# OtherSensors.net
KiCad netlist of a schematic drawn in Altium Designer
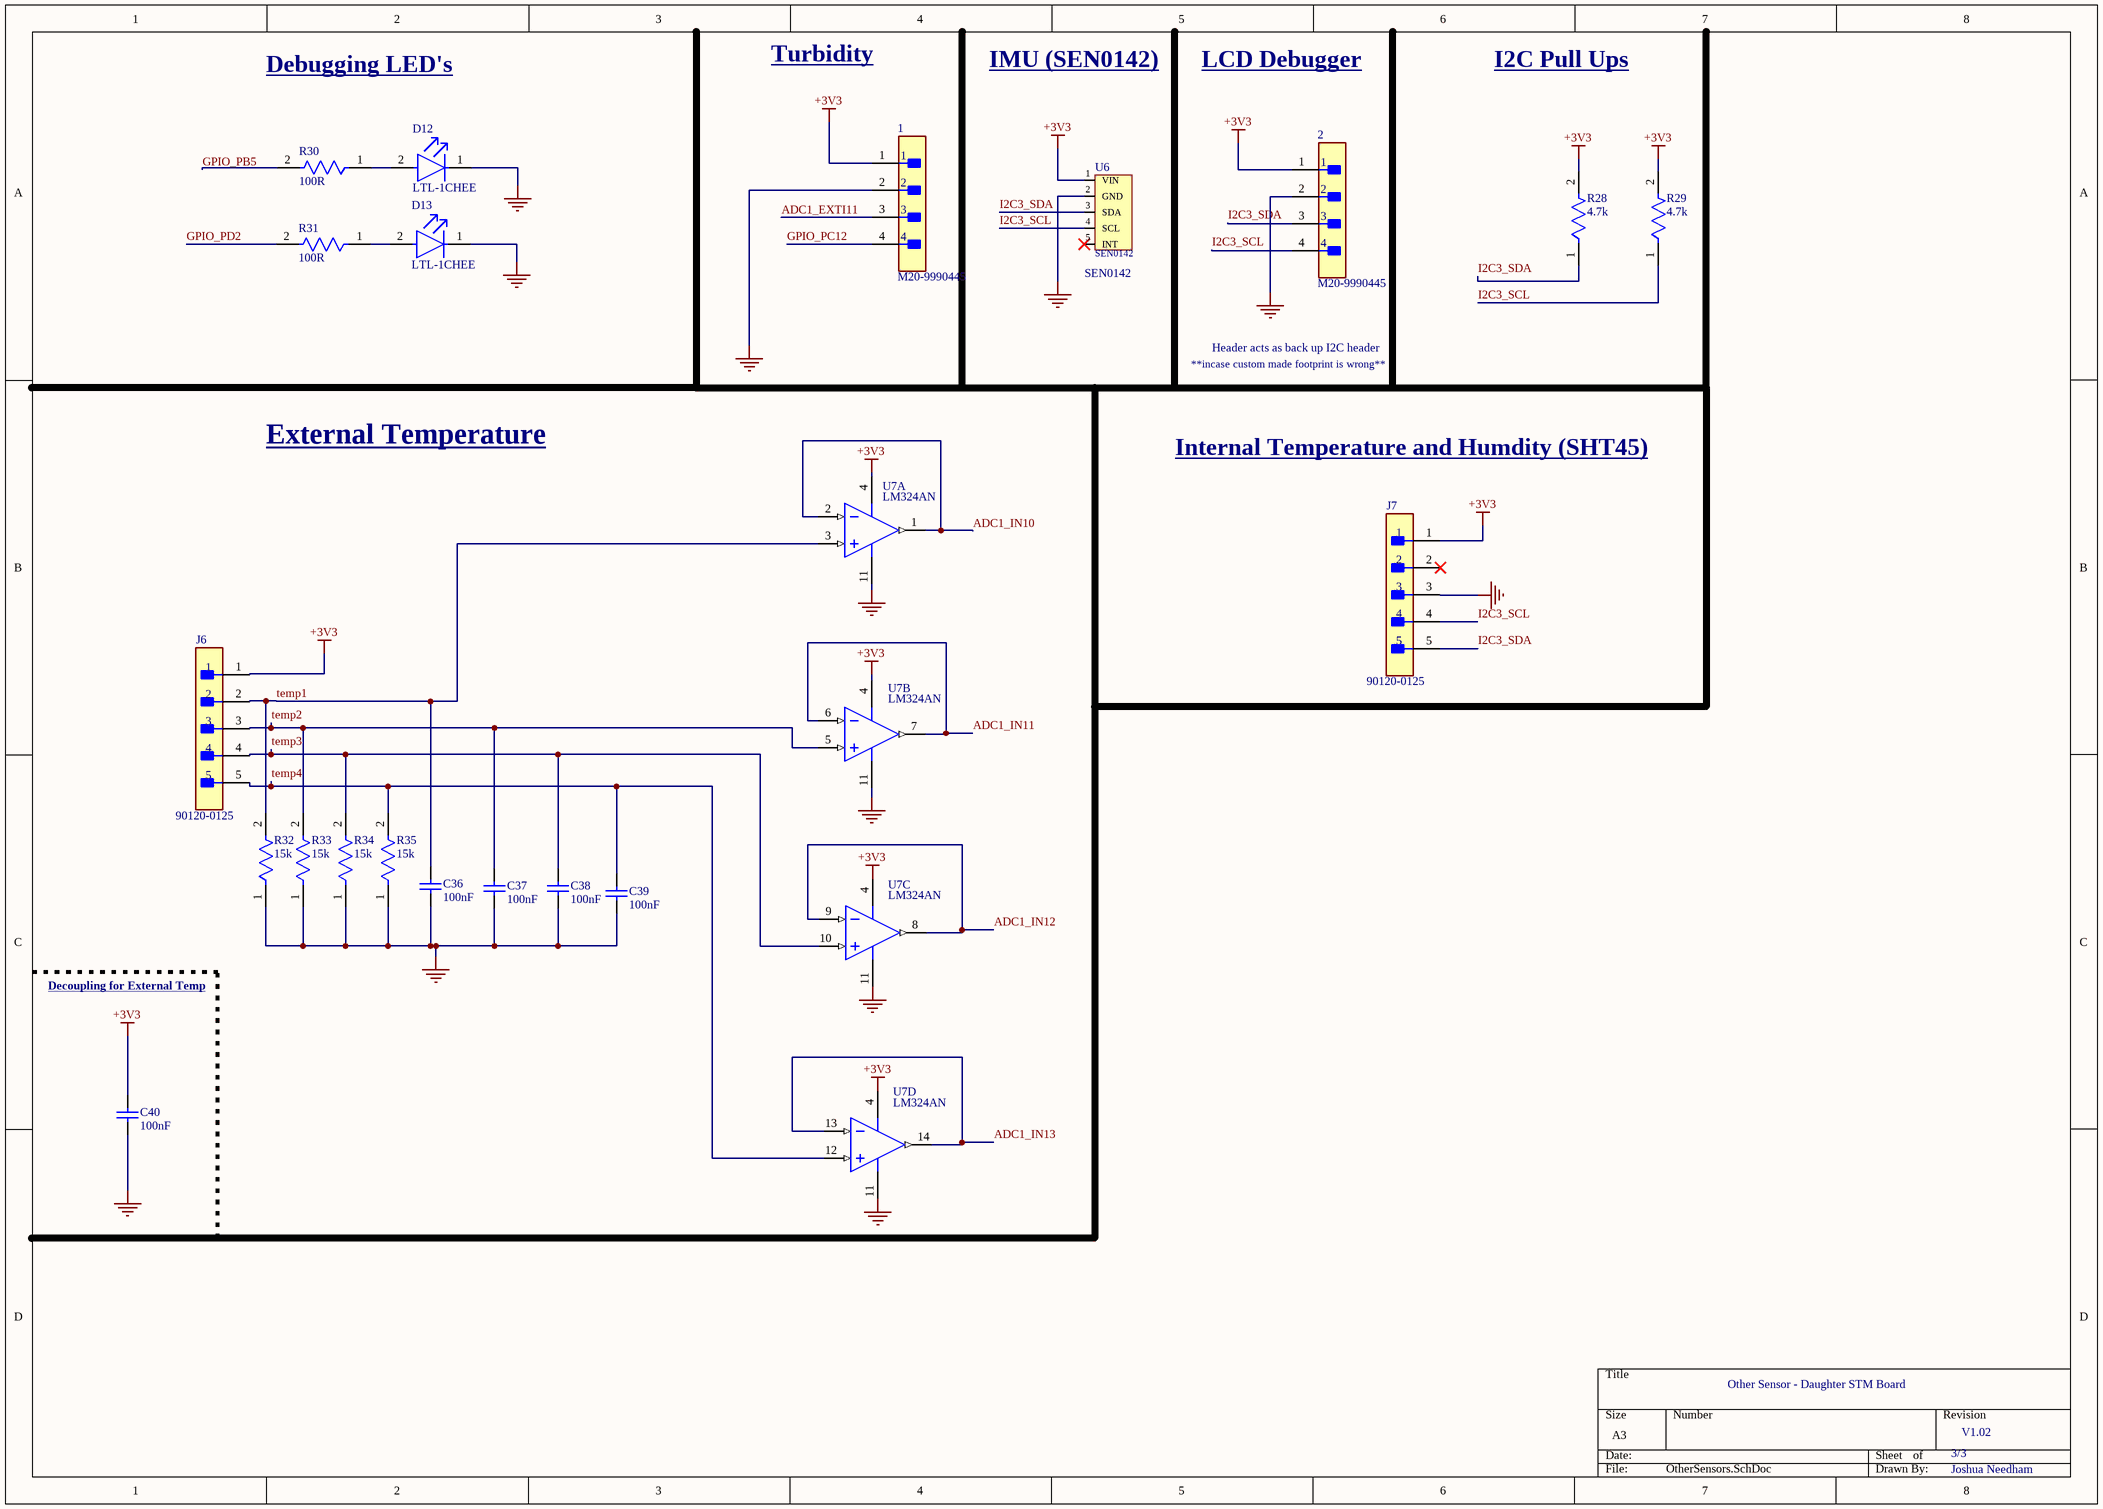
[diagram p0: OtherSensors.SchDoc]

(export (version "E")
  (design (tool "Eeschema 10.0.6"))
  (components
    (comp (ref "1")
      (value "M20-9990445")
      (footprint "FP-M20-9990445-MFG")
      (description "M20-9990445 Conn Unshrouded Header HDR 4 POS 2.54mm Solder ST Thru-Hole Bulk/Loose")
      (libsource (lib "Altium Content Vault") (part "299a8cea1bdcbc3624fe62c390fa72c"))
    )
    (comp (ref "2")
      (value "M20-9990445")
      (footprint "FP-M20-9990445-MFG")
      (description "M20-9990445 Conn Unshrouded Header HDR 4 POS 2.54mm Solder ST Thru-Hole Bulk/Loose")
      (libsource (lib "Altium Content Vault") (part "299a8cea1bdcbc3624fe62c390fa72c"))
    )
    (comp (ref "C36")
      (value "100nF")
      (footprint "CAPC0805(2012)100_M")
      (description "CAP 100nF 10V ±5% 0805 (2012 Metric) Thickness 1mm SMD")
      (fields (field (name "TOLERANCE") "Â±5%"))
      (libsource (lib "Altium Content Vault") (part "CAP"))
    )
    (comp (ref "C37")
      (value "100nF")
      (footprint "CAPC0805(2012)100_M")
      (description "CAP 100nF 10V ±5% 0805 (2012 Metric) Thickness 1mm SMD")
      (fields (field (name "TOLERANCE") "Â±5%"))
      (libsource (lib "Altium Content Vault") (part "CAP"))
    )
    (comp (ref "C38")
      (value "100nF")
      (footprint "CAPC0805(2012)100_M")
      (description "CAP 100nF 10V ±5% 0805 (2012 Metric) Thickness 1mm SMD")
      (fields (field (name "TOLERANCE") "Â±5%"))
      (libsource (lib "Altium Content Vault") (part "CAP"))
    )
    (comp (ref "C39")
      (value "100nF")
      (footprint "CAPC0805(2012)100_M")
      (description "CAP 100nF 10V ±5% 0805 (2012 Metric) Thickness 1mm SMD")
      (fields (field (name "TOLERANCE") "Â±5%"))
      (libsource (lib "Altium Content Vault") (part "CAP"))
    )
    (comp (ref "C40")
      (value "100nF")
      (footprint "CAPC0805(2012)100_M")
      (description "CAP 100nF 10V ±5% 0805 (2012 Metric) Thickness 1mm SMD")
      (fields (field (name "TOLERANCE") "Â±5%"))
      (libsource (lib "Altium Content Vault") (part "CAP"))
    )
    (comp (ref "D12")
      (value "LTL-1CHEE")
      (footprint "FP-LTL-1CHEE-MFG")
      (description "LED RED CLEAR T/H")
      (libsource (lib "Altium Content Vault") (part "8706943c75ba83719d021d2fdc84c58"))
    )
    (comp (ref "D13")
      (value "LTL-1CHEE")
      (footprint "FP-LTL-1CHEE-MFG")
      (description "LED RED CLEAR T/H")
      (libsource (lib "Altium Content Vault") (part "8706943c75ba83719d021d2fdc84c58"))
    )
    (comp (ref "J6")
      (value "90120-0125")
      (footprint "FP-90120-0125-MFG")
      (description "90120-0125 2.54mm Pitch C-Grid III Header, Single Row, Vertical, 5 Circuits, Tin (Sn) Plating")
      (libsource (lib "Altium Content Vault") (part "bf93c07fd2649a848d0ec8585582aab"))
    )
    (comp (ref "J7")
      (value "90120-0125")
      (footprint "FP-90120-0125-MFG")
      (description "90120-0125 2.54mm Pitch C-Grid III Header, Single Row, Vertical, 5 Circuits, Tin (Sn) Plating")
      (libsource (lib "Altium Content Vault") (part "bf93c07fd2649a848d0ec8585582aab"))
    )
    (comp (ref "R28")
      (value "4.7k")
      (footprint "FP-CRCW0805-e3-IPC_A")
      (description "RES Thick Film, 680Ω, 5%, 0.125W, 200ppm/°C, 0805")
      (fields (field (name "TOLERANCE") "5%"))
      (libsource (lib "Altium Content Vault") (part "1029c3af85768c4190bb7ad29bc67b5"))
    )
    (comp (ref "R29")
      (value "4.7k")
      (footprint "FP-CRCW0805-e3-IPC_A")
      (description "RES Thick Film, 680Ω, 5%, 0.125W, 200ppm/°C, 0805")
      (fields (field (name "TOLERANCE") "5%"))
      (libsource (lib "Altium Content Vault") (part "1029c3af85768c4190bb7ad29bc67b5"))
    )
    (comp (ref "R30")
      (value "100R")
      (footprint "FP-CRCW0805-e3-IPC_A")
      (description "RES Thick Film, 680Ω, 5%, 0.125W, 200ppm/°C, 0805")
      (fields (field (name "TOLERANCE") "5%"))
      (libsource (lib "Altium Content Vault") (part "1029c3af85768c4190bb7ad29bc67b5"))
    )
    (comp (ref "R31")
      (value "100R")
      (footprint "FP-CRCW0805-e3-IPC_A")
      (description "RES Thick Film, 680Ω, 5%, 0.125W, 200ppm/°C, 0805")
      (fields (field (name "TOLERANCE") "5%"))
      (libsource (lib "Altium Content Vault") (part "1029c3af85768c4190bb7ad29bc67b5"))
    )
    (comp (ref "R32")
      (value "15k")
      (footprint "FP-CRCW0805-e3-IPC_A")
      (description "RES Thick Film, 680Ω, 5%, 0.125W, 200ppm/°C, 0805")
      (fields (field (name "TOLERANCE") "5%"))
      (libsource (lib "Altium Content Vault") (part "1029c3af85768c4190bb7ad29bc67b5"))
    )
    (comp (ref "R33")
      (value "15k")
      (footprint "FP-CRCW0805-e3-IPC_A")
      (description "RES Thick Film, 680Ω, 5%, 0.125W, 200ppm/°C, 0805")
      (fields (field (name "TOLERANCE") "5%"))
      (libsource (lib "Altium Content Vault") (part "1029c3af85768c4190bb7ad29bc67b5"))
    )
    (comp (ref "R34")
      (value "15k")
      (footprint "FP-CRCW0805-e3-IPC_A")
      (description "RES Thick Film, 680Ω, 5%, 0.125W, 200ppm/°C, 0805")
      (fields (field (name "TOLERANCE") "5%"))
      (libsource (lib "Altium Content Vault") (part "1029c3af85768c4190bb7ad29bc67b5"))
    )
    (comp (ref "R35")
      (value "15k")
      (footprint "FP-CRCW0805-e3-IPC_A")
      (description "RES Thick Film, 680Ω, 5%, 0.125W, 200ppm/°C, 0805")
      (fields (field (name "TOLERANCE") "5%"))
      (libsource (lib "Altium Content Vault") (part "1029c3af85768c4190bb7ad29bc67b5"))
    )
    (comp (ref "U6")
      (value "SEN0142")
      (footprint "PCBComponent_1")
      (description "6 axis IMU")
      (libsource (lib "IMU") (part "SEN0142"))
    )
    (comp (ref "U7")
      (value "LM324AN")
      (footprint "N0014A")
      (description "Low Power Quad Operational Amplifier, 14-pin MDIP")
      (fields (field (name "MANUFACTURER") "Texas Instruments"))
      (libsource (lib "Altium Content Vault") (part "AMP-OPA-LM124-14"))
    )
  )
  (nets
    (net (code "1") (name "+3V3") (class "Default")
      (node (ref "1") (pin "1") (pinfunction "1_1") (pintype "passive"))
      (node (ref "2") (pin "1") (pinfunction "1_1") (pintype "passive"))
      (node (ref "C40") (pin "2") (pinfunction "2_2") (pintype "passive"))
      (node (ref "J6") (pin "1") (pinfunction "1_1") (pintype "passive"))
      (node (ref "J7") (pin "1") (pinfunction "1_1") (pintype "passive"))
      (node (ref "R28") (pin "2") (pinfunction "2_2") (pintype "passive"))
      (node (ref "R29") (pin "2") (pinfunction "2_2") (pintype "passive"))
      (node (ref "U6") (pin "1") (pinfunction "VIN_1") (pintype "power_in"))
      (node (ref "U7") (pin "4") (pinfunction "V+_4") (pintype "power_in"))
    )
    (net (code "2") (name "/ADC1_EXTI11") (class "Default")
      (node (ref "1") (pin "3") (pinfunction "3_3") (pintype "passive"))
    )
    (net (code "3") (name "/ADC1_IN10") (class "Default")
      (node (ref "U7") (pin "1") (pinfunction "OUT1_1") (pintype "output"))
      (node (ref "U7") (pin "2") (pinfunction "IN1-_2") (pintype "input"))
    )
    (net (code "4") (name "/ADC1_IN11") (class "Default")
      (node (ref "U7") (pin "6") (pinfunction "IN2-_6") (pintype "input"))
      (node (ref "U7") (pin "7") (pinfunction "OUT2_7") (pintype "output"))
    )
    (net (code "5") (name "/ADC1_IN12") (class "Default")
      (node (ref "U7") (pin "8") (pinfunction "OUT3_8") (pintype "output"))
      (node (ref "U7") (pin "9") (pinfunction "IN3-_9") (pintype "input"))
    )
    (net (code "6") (name "/ADC1_IN13") (class "Default")
      (node (ref "U7") (pin "13") (pinfunction "IN4-_13") (pintype "input"))
      (node (ref "U7") (pin "14") (pinfunction "OUT4_14") (pintype "output"))
    )
    (net (code "7") (name "/GPIO_PB5") (class "Default")
      (node (ref "R30") (pin "2") (pinfunction "2_2") (pintype "passive"))
    )
    (net (code "8") (name "/GPIO_PC12") (class "Default")
      (node (ref "1") (pin "4") (pinfunction "4_4") (pintype "passive"))
    )
    (net (code "9") (name "/GPIO_PD2") (class "Default")
      (node (ref "R31") (pin "2") (pinfunction "2_2") (pintype "passive"))
    )
    (net (code "10") (name "/I2C3_SCL") (class "Default")
      (node (ref "2") (pin "4") (pinfunction "4_4") (pintype "passive"))
      (node (ref "J7") (pin "4") (pinfunction "4_4") (pintype "passive"))
      (node (ref "R29") (pin "1") (pinfunction "1_1") (pintype "passive"))
      (node (ref "U6") (pin "4") (pinfunction "SCL_4") (pintype "passive"))
    )
    (net (code "11") (name "/I2C3_SDA") (class "Default")
      (node (ref "2") (pin "3") (pinfunction "3_3") (pintype "passive"))
      (node (ref "J7") (pin "5") (pinfunction "5_5") (pintype "passive"))
      (node (ref "R28") (pin "1") (pinfunction "1_1") (pintype "passive"))
      (node (ref "U6") (pin "3") (pinfunction "SDA_3") (pintype "passive"))
    )
    (net (code "12") (name "/temp1") (class "Default")
      (node (ref "C36") (pin "2") (pinfunction "2_2") (pintype "passive"))
      (node (ref "J6") (pin "2") (pinfunction "2_2") (pintype "passive"))
      (node (ref "R32") (pin "2") (pinfunction "2_2") (pintype "passive"))
      (node (ref "U7") (pin "3") (pinfunction "IN1+_3") (pintype "input"))
    )
    (net (code "13") (name "/temp2") (class "Default")
      (node (ref "C37") (pin "2") (pinfunction "2_2") (pintype "passive"))
      (node (ref "J6") (pin "3") (pinfunction "3_3") (pintype "passive"))
      (node (ref "R33") (pin "2") (pinfunction "2_2") (pintype "passive"))
      (node (ref "U7") (pin "5") (pinfunction "IN2+_5") (pintype "input"))
    )
    (net (code "14") (name "/temp3") (class "Default")
      (node (ref "C38") (pin "2") (pinfunction "2_2") (pintype "passive"))
      (node (ref "J6") (pin "4") (pinfunction "4_4") (pintype "passive"))
      (node (ref "R34") (pin "2") (pinfunction "2_2") (pintype "passive"))
      (node (ref "U7") (pin "10") (pinfunction "IN3+_10") (pintype "input"))
    )
    (net (code "15") (name "/temp4") (class "Default")
      (node (ref "C39") (pin "2") (pinfunction "2_2") (pintype "passive"))
      (node (ref "J6") (pin "5") (pinfunction "5_5") (pintype "passive"))
      (node (ref "R35") (pin "2") (pinfunction "2_2") (pintype "passive"))
      (node (ref "U7") (pin "12") (pinfunction "IN4+_12") (pintype "input"))
    )
    (net (code "16") (name "GND") (class "Default")
      (node (ref "1") (pin "2") (pinfunction "2_2") (pintype "passive"))
      (node (ref "2") (pin "2") (pinfunction "2_2") (pintype "passive"))
      (node (ref "C36") (pin "1") (pinfunction "1_1") (pintype "passive"))
      (node (ref "C37") (pin "1") (pinfunction "1_1") (pintype "passive"))
      (node (ref "C38") (pin "1") (pinfunction "1_1") (pintype "passive"))
      (node (ref "C39") (pin "1") (pinfunction "1_1") (pintype "passive"))
      (node (ref "C40") (pin "1") (pinfunction "1_1") (pintype "passive"))
      (node (ref "D12") (pin "1") (pinfunction "C_1") (pintype "passive"))
      (node (ref "D13") (pin "1") (pinfunction "C_1") (pintype "passive"))
      (node (ref "J7") (pin "3") (pinfunction "3_3") (pintype "passive"))
      (node (ref "R32") (pin "1") (pinfunction "1_1") (pintype "passive"))
      (node (ref "R33") (pin "1") (pinfunction "1_1") (pintype "passive"))
      (node (ref "R34") (pin "1") (pinfunction "1_1") (pintype "passive"))
      (node (ref "R35") (pin "1") (pinfunction "1_1") (pintype "passive"))
      (node (ref "U6") (pin "2") (pinfunction "GND_2") (pintype "passive"))
      (node (ref "U7") (pin "11") (pinfunction "GND_11") (pintype "power_in"))
    )
    (net (code "17") (name "Net-(D12-A)") (class "Default")
      (node (ref "D12") (pin "2") (pinfunction "A_2") (pintype "passive"))
      (node (ref "R30") (pin "1") (pinfunction "1_1") (pintype "passive"))
    )
    (net (code "18") (name "Net-(D13-A)") (class "Default")
      (node (ref "D13") (pin "2") (pinfunction "A_2") (pintype "passive"))
      (node (ref "R31") (pin "1") (pinfunction "1_1") (pintype "passive"))
    )
    (net (code "19") (name "unconnected-(J7-Pad2)") (class "Default")
      (node (ref "J7") (pin "2") (pinfunction "2_2") (pintype "passive+no_connect"))
    )
    (net (code "20") (name "unconnected-(U6-INT-Pad5)") (class "Default")
      (node (ref "U6") (pin "5") (pinfunction "INT_5") (pintype "passive+no_connect"))
    )
  )
)
